# interstage_A2v2.net
KiCad netlist of a schematic drawn in EAGLE
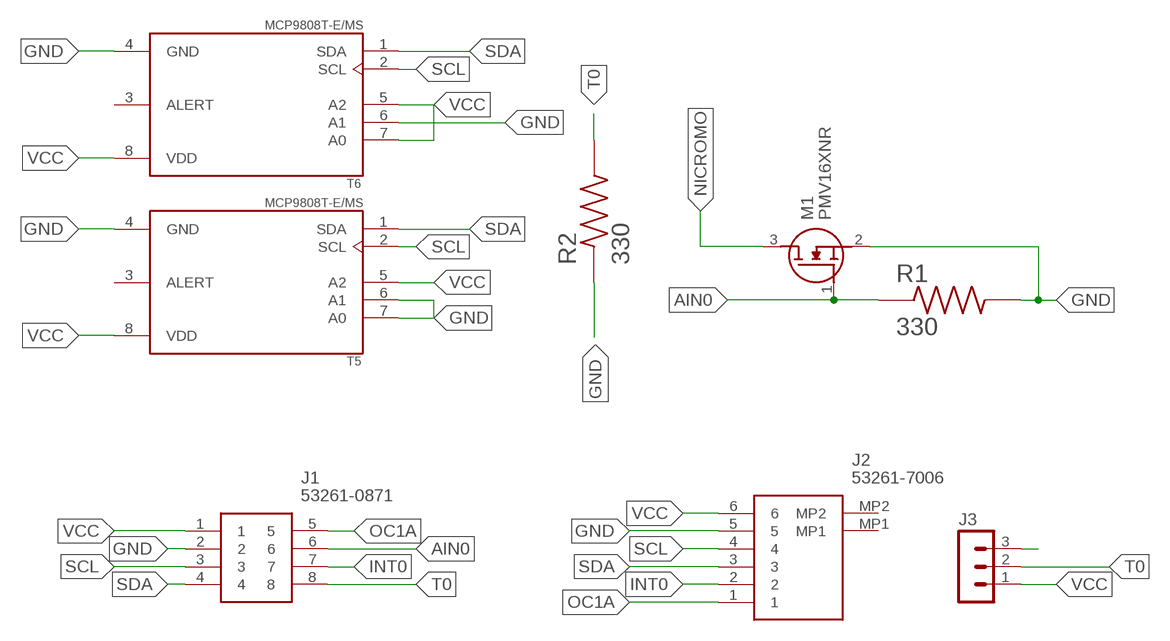
[diagram p0: schematic, sheet 1]

(export (version "E")
  (design (tool "Eeschema 10.0.6"))
  (components
    (comp (ref "J1")
      (value "53261-0871")
      (footprint "eagle-import:53261-0871")
      (fields (field (name "MOUSER_PART_NUMBER") "538-53261-0871"))
      (libsource (lib "eagle-import") (part "53261-0871"))
    )
    (comp (ref "J2")
      (value "53261-7006")
      (footprint "eagle-import:532617006")
      (fields (field (name "MOUSER_PART_NUMBER") "538-53261-7006"))
      (libsource (lib "eagle-import") (part "53261-7006"))
    )
    (comp (ref "J3")
      (value "MA03-1")
      (footprint "eagle-import:MA03-1")
      (libsource (lib "eagle-import") (part "MA03-1"))
    )
    (comp (ref "M1")
      (value "PMV16XNR")
      (footprint "eagle-import:SOT95P230X110-3N")
      (fields (field (name "MOUSER_PART_NUMBER") "771-PMV16XNR"))
      (libsource (lib "eagle-import") (part "PMV16XNR"))
    )
    (comp (ref "R1")
      (value "330")
      (footprint "eagle-import:RESC3216X70N")
      (fields
        (field (name "DIGI-KEY_PART_NUMBER") "P330BCCT-ND")
        (field (name "MF") "Panasonic Electronic")
        (field (name "MP") "ERA-8AEB331V")
      )
      (libsource (lib "eagle-import") (part "ERA-8AEB331V"))
    )
    (comp (ref "R2")
      (value "330")
      (footprint "eagle-import:RESC3216X70N")
      (fields
        (field (name "DIGI-KEY_PART_NUMBER") "P330BCCT-ND")
        (field (name "MF") "Panasonic Electronic")
        (field (name "MP") "ERA-8AEB331V")
      )
      (libsource (lib "eagle-import") (part "ERA-8AEB331V"))
    )
    (comp (ref "T5")
      (value "MCP9808T-E/MS")
      (footprint "eagle-import:SOP65P490X110-8N")
      (fields (field (name "DIGI-KEY_PART_NUMBER") "MCP9808T-E/MSCT-ND") (field (name "MF") "Microchip"))
      (libsource (lib "eagle-import") (part "MCP9808T-E/MS"))
    )
    (comp (ref "T6")
      (value "MCP9808T-E/MS")
      (footprint "eagle-import:SOP65P490X110-8N")
      (fields (field (name "DIGI-KEY_PART_NUMBER") "MCP9808T-E/MSCT-ND") (field (name "MF") "Microchip"))
      (libsource (lib "eagle-import") (part "MCP9808T-E/MS"))
    )
  )
  (nets
    (net (code "1") (name "AIN0") (class "Default")
      (node (ref "J1") (pin "6") (pinfunction "6_6") (pintype "bidirectional"))
      (node (ref "M1") (pin "1") (pinfunction "G_1") (pintype "bidirectional"))
      (node (ref "R1") (pin "1") (pinfunction "1_1") (pintype "passive"))
    )
    (net (code "2") (name "GND") (class "Default")
      (node (ref "J1") (pin "2") (pinfunction "2_2") (pintype "bidirectional"))
      (node (ref "J2") (pin "5") (pinfunction "5_5") (pintype "bidirectional"))
      (node (ref "M1") (pin "2") (pinfunction "S_2") (pintype "bidirectional"))
      (node (ref "R1") (pin "2") (pinfunction "2_2") (pintype "passive"))
      (node (ref "R2") (pin "1") (pinfunction "1_1") (pintype "passive"))
      (node (ref "T5") (pin "4") (pinfunction "GND_4") (pintype "power_in"))
      (node (ref "T5") (pin "6") (pinfunction "A1_6") (pintype "input"))
      (node (ref "T5") (pin "7") (pinfunction "A0_7") (pintype "input"))
      (node (ref "T6") (pin "4") (pinfunction "GND_4") (pintype "power_in"))
      (node (ref "T6") (pin "6") (pinfunction "A1_6") (pintype "input"))
    )
    (net (code "3") (name "INT0") (class "Default")
      (node (ref "J1") (pin "7") (pinfunction "7_7") (pintype "bidirectional"))
      (node (ref "J2") (pin "2") (pinfunction "2_2") (pintype "bidirectional"))
    )
    (net (code "4") (name "NICROMO") (class "Default")
      (node (ref "M1") (pin "3") (pinfunction "D_3") (pintype "bidirectional"))
    )
    (net (code "5") (name "OC1A") (class "Default")
      (node (ref "J1") (pin "5") (pinfunction "5_5") (pintype "bidirectional"))
      (node (ref "J2") (pin "1") (pinfunction "1_1") (pintype "bidirectional"))
    )
    (net (code "6") (name "SCL") (class "Default")
      (node (ref "J1") (pin "3") (pinfunction "3_3") (pintype "bidirectional"))
      (node (ref "J2") (pin "4") (pinfunction "4_4") (pintype "bidirectional"))
      (node (ref "T5") (pin "2") (pinfunction "SCL_2") (pintype "input"))
      (node (ref "T6") (pin "2") (pinfunction "SCL_2") (pintype "input"))
    )
    (net (code "7") (name "SDA") (class "Default")
      (node (ref "J1") (pin "4") (pinfunction "4_4") (pintype "bidirectional"))
      (node (ref "J2") (pin "3") (pinfunction "3_3") (pintype "bidirectional"))
      (node (ref "T5") (pin "1") (pinfunction "SDA_1") (pintype "bidirectional"))
      (node (ref "T6") (pin "1") (pinfunction "SDA_1") (pintype "bidirectional"))
    )
    (net (code "8") (name "T0") (class "Default")
      (node (ref "J1") (pin "8") (pinfunction "8_8") (pintype "bidirectional"))
      (node (ref "J3") (pin "2") (pinfunction "2_2") (pintype "passive"))
      (node (ref "R2") (pin "2") (pinfunction "2_2") (pintype "passive"))
    )
    (net (code "9") (name "VCC") (class "Default")
      (node (ref "J1") (pin "1") (pinfunction "1_1") (pintype "bidirectional"))
      (node (ref "J2") (pin "6") (pinfunction "6_6") (pintype "bidirectional"))
      (node (ref "J3") (pin "1") (pinfunction "1_1") (pintype "passive"))
      (node (ref "T5") (pin "5") (pinfunction "A2_5") (pintype "input"))
      (node (ref "T5") (pin "8") (pinfunction "VDD_8") (pintype "power_in"))
      (node (ref "T6") (pin "5") (pinfunction "A2_5") (pintype "input"))
      (node (ref "T6") (pin "7") (pinfunction "A0_7") (pintype "input"))
      (node (ref "T6") (pin "8") (pinfunction "VDD_8") (pintype "power_in"))
    )
    (net (code "10") (name "unconnected-(J2-PadMP1)") (class "Default")
      (node (ref "J2") (pin "MP1") (pinfunction "MP1_MP1") (pintype "bidirectional"))
    )
    (net (code "11") (name "unconnected-(J2-PadMP2)") (class "Default")
      (node (ref "J2") (pin "MP2") (pinfunction "MP2_MP2") (pintype "bidirectional"))
    )
    (net (code "12") (name "unconnected-(J3-Pad3)") (class "Default")
      (node (ref "J3") (pin "3") (pinfunction "3_3") (pintype "passive"))
    )
    (net (code "13") (name "unconnected-(T5-ALERT-Pad3)") (class "Default")
      (node (ref "T5") (pin "3") (pinfunction "ALERT_3") (pintype "output"))
    )
    (net (code "14") (name "unconnected-(T6-ALERT-Pad3)") (class "Default")
      (node (ref "T6") (pin "3") (pinfunction "ALERT_3") (pintype "output"))
    )
  )
)
